# ChargeControllerMainBoard.net
KiCad netlist of a schematic drawn in EAGLE
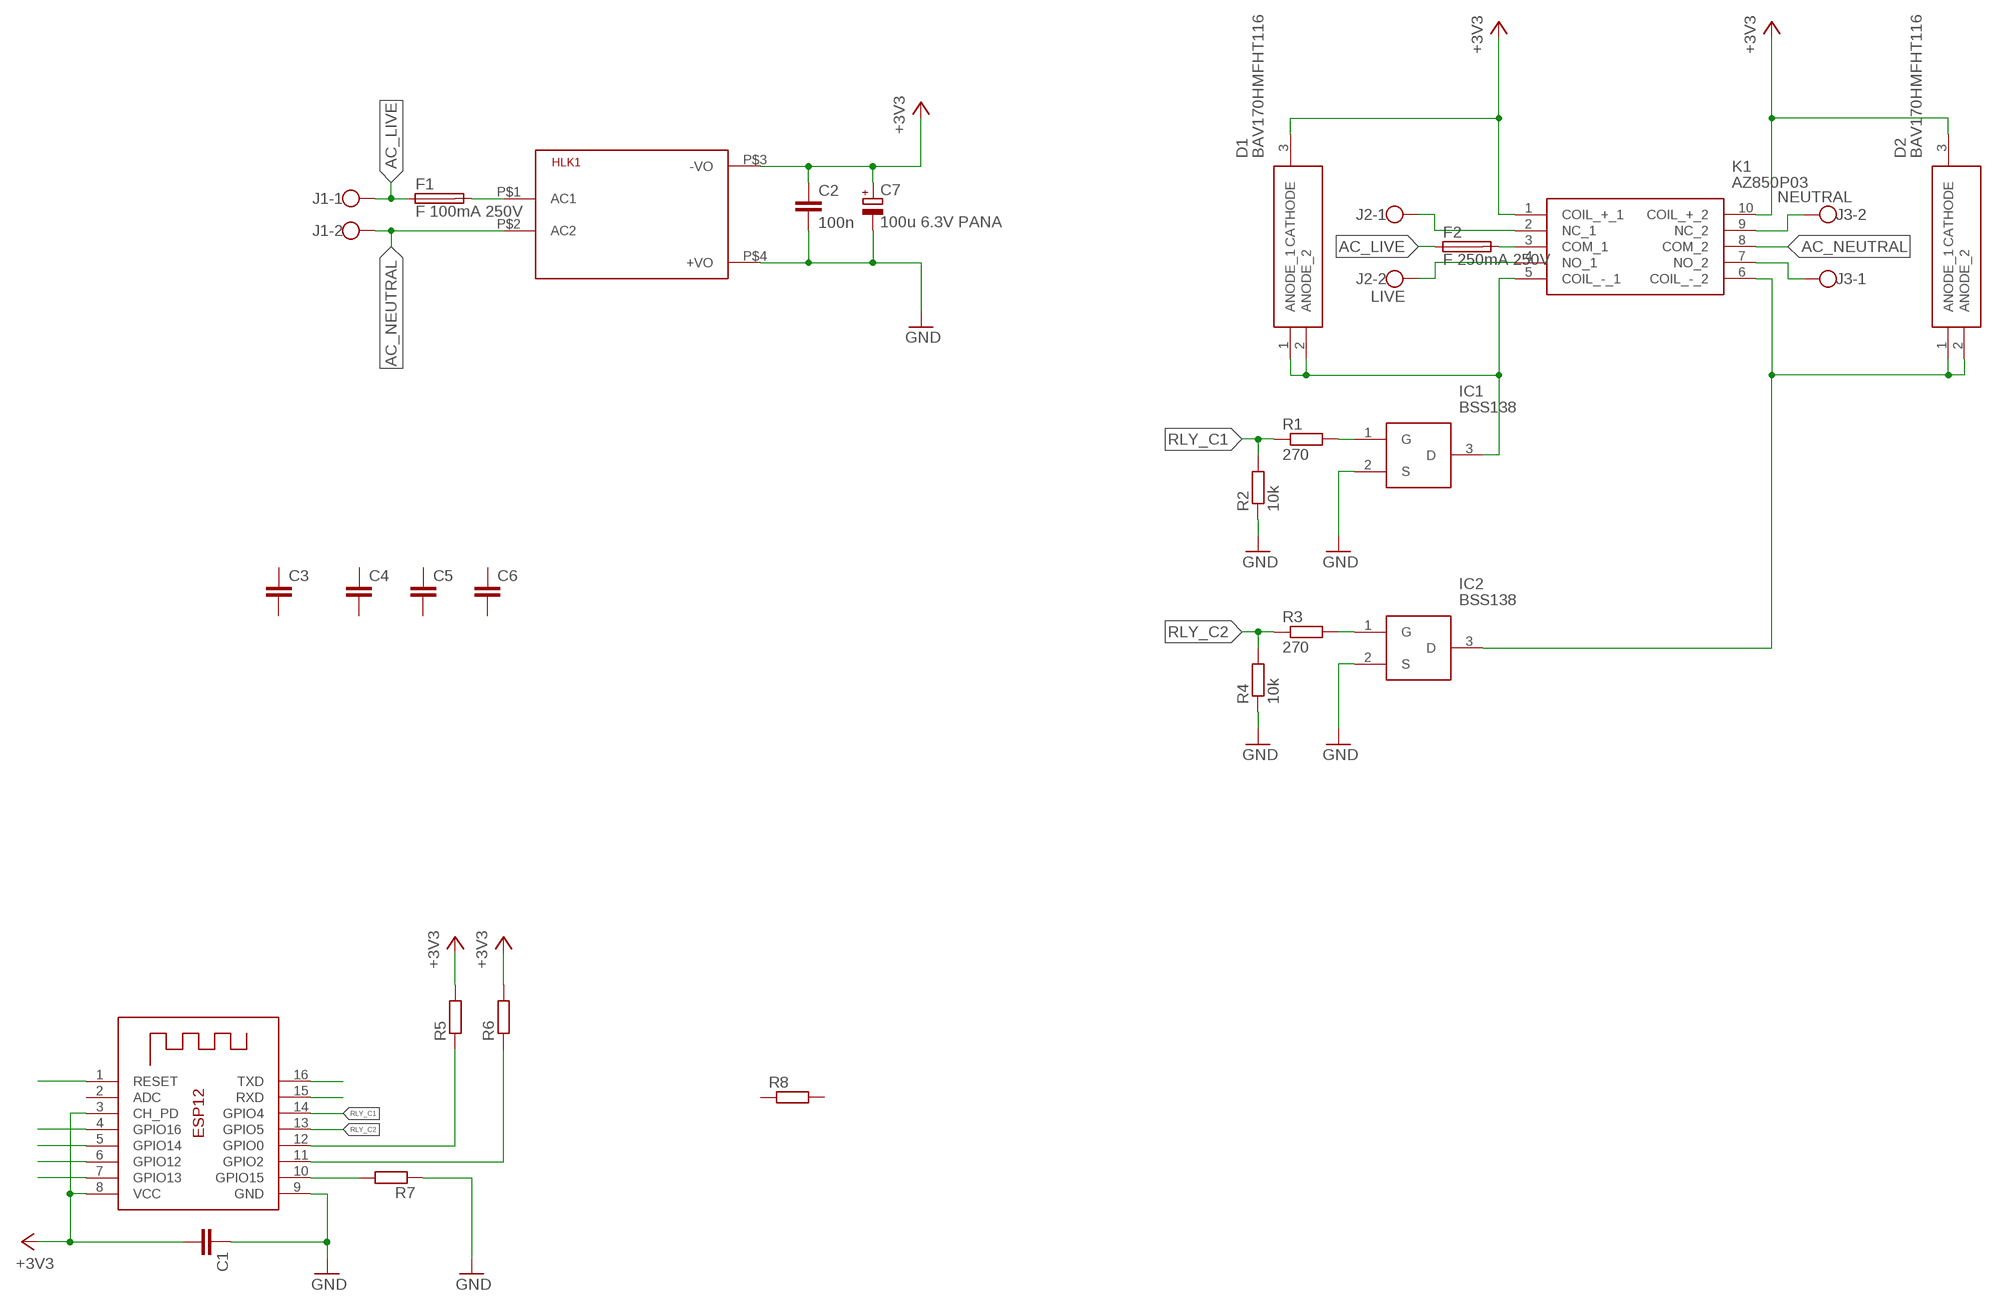
[diagram p0: schematic, sheet 1]

(export (version "E")
  (design (tool "Eeschema 10.0.6"))
  (components
    (comp (ref "C1")
      (value "C-EUC0805")
      (footprint "eagle-import:C0805")
      (libsource (lib "eagle-import") (part "C-EUC0805"))
    )
    (comp (ref "C2")
      (value "100n")
      (footprint "eagle-import:C0805")
      (libsource (lib "eagle-import") (part "C-EUC0805"))
    )
    (comp (ref "C3")
      (value "C-EUC0805")
      (footprint "eagle-import:C0805")
      (libsource (lib "eagle-import") (part "C-EUC0805"))
    )
    (comp (ref "C4")
      (value "C-EUC0805")
      (footprint "eagle-import:C0805")
      (libsource (lib "eagle-import") (part "C-EUC0805"))
    )
    (comp (ref "C5")
      (value "C-EUC0805")
      (footprint "eagle-import:C0805")
      (libsource (lib "eagle-import") (part "C-EUC0805"))
    )
    (comp (ref "C6")
      (value "C-EUC0805")
      (footprint "eagle-import:C0805")
      (libsource (lib "eagle-import") (part "C-EUC0805"))
    )
    (comp (ref "C7")
      (value "100u 6.3V PANA")
      (footprint "eagle-import:PANASONIC_B")
      (libsource (lib "eagle-import") (part "CPOL-EUB"))
    )
    (comp (ref "D1")
      (value "BAV170HMFHT116")
      (footprint "eagle-import:SOT95P240X115-3N")
      (fields (field (name "MOUSER_PART_NUMBER") "755-BAV170HMFHT116"))
      (libsource (lib "eagle-import") (part "BAV170HMFHT116"))
    )
    (comp (ref "D2")
      (value "BAV170HMFHT116")
      (footprint "eagle-import:SOT95P240X115-3N")
      (fields (field (name "MOUSER_PART_NUMBER") "755-BAV170HMFHT116"))
      (libsource (lib "eagle-import") (part "BAV170HMFHT116"))
    )
    (comp (ref "F1")
      (value "F 100mA 250V")
      (footprint "eagle-import:SH22,5")
      (fields (field (name "MF") "SCHURTER") (field (name "MPN") "0031.8201"))
      (libsource (lib "eagle-import") (part "SH22,5"))
    )
    (comp (ref "F2")
      (value "F 250mA 250V")
      (footprint "eagle-import:SH22,5")
      (fields (field (name "MF") "SCHURTER") (field (name "MPN") "0031.8201"))
      (libsource (lib "eagle-import") (part "SH22,5"))
    )
    (comp (ref "HLK1")
      (value "HLK-PM03")
      (footprint "eagle-import:HLK-PM01")
      (libsource (lib "eagle-import") (part "HLK-PM013W"))
    )
    (comp (ref "IC1")
      (value "BSS138")
      (footprint "eagle-import:SOT95P240X120-3N")
      (fields (field (name "MOUSER_PART_NUMBER") "512-BSS138") (field (name "RS_PART_NUMBER") "1241694"))
      (libsource (lib "eagle-import") (part "BSS138"))
    )
    (comp (ref "IC2")
      (value "BSS138")
      (footprint "eagle-import:SOT95P240X120-3N")
      (fields (field (name "MOUSER_PART_NUMBER") "512-BSS138") (field (name "RS_PART_NUMBER") "1241694"))
      (libsource (lib "eagle-import") (part "BSS138"))
    )
    (comp (ref "J1")
      (value "W237-102")
      (footprint "eagle-import:W237-102")
      (fields (field (name "MPN") "237-102"))
      (libsource (lib "eagle-import") (part "W237-102"))
    )
    (comp (ref "J2")
      (value "LIVE")
      (footprint "eagle-import:W237-102")
      (fields (field (name "MPN") "237-102"))
      (libsource (lib "eagle-import") (part "W237-102"))
    )
    (comp (ref "J3")
      (value "NEUTRAL")
      (footprint "eagle-import:W237-102")
      (fields (field (name "MPN") "237-102"))
      (libsource (lib "eagle-import") (part "W237-102"))
    )
    (comp (ref "K1")
      (value "AZ850P03")
      (footprint "eagle-import:DIPS763W51P254L1400H525Q10N")
      (fields (field (name "MANUFACTURER_PART_NUMBER") "AZ850P2&ndash;5"))
      (libsource (lib "eagle-import") (part "AZ850P25"))
    )
    (comp (ref "R1")
      (value "270")
      (footprint "eagle-import:R0805")
      (libsource (lib "eagle-import") (part "R-EU_R0805"))
    )
    (comp (ref "R2")
      (value "10k")
      (footprint "eagle-import:R0805")
      (libsource (lib "eagle-import") (part "R-EU_R0805"))
    )
    (comp (ref "R3")
      (value "270")
      (footprint "eagle-import:R0805")
      (libsource (lib "eagle-import") (part "R-EU_R0805"))
    )
    (comp (ref "R4")
      (value "10k")
      (footprint "eagle-import:R0805")
      (libsource (lib "eagle-import") (part "R-EU_R0805"))
    )
    (comp (ref "R5")
      (value "R-EU_R0805")
      (footprint "eagle-import:R0805")
      (libsource (lib "eagle-import") (part "R-EU_R0805"))
    )
    (comp (ref "R6")
      (value "R-EU_R0805")
      (footprint "eagle-import:R0805")
      (libsource (lib "eagle-import") (part "R-EU_R0805"))
    )
    (comp (ref "R7")
      (value "R-EU_R0805")
      (footprint "eagle-import:R0805")
      (libsource (lib "eagle-import") (part "R-EU_R0805"))
    )
    (comp (ref "R8")
      (value "R-EU_R0805")
      (footprint "eagle-import:R0805")
      (libsource (lib "eagle-import") (part "R-EU_R0805"))
    )
    (comp (ref "X1")
      (value "ESP-12")
      (footprint "eagle-import:ESP-12")
      (libsource (lib "eagle-import") (part "ESP-12"))
    )
  )
  (nets
    (net (code "1") (name "+3V3") (class "Default")
      (node (ref "C1") (pin "2") (pinfunction "2_2") (pintype "passive"))
      (node (ref "C2") (pin "1") (pinfunction "1_1") (pintype "passive"))
      (node (ref "C7") (pin "+") (pinfunction "+_+") (pintype "passive"))
      (node (ref "D1") (pin "3") (pinfunction "CATHODE_3") (pintype "bidirectional"))
      (node (ref "D2") (pin "3") (pinfunction "CATHODE_3") (pintype "bidirectional"))
      (node (ref "HLK1") (pin "P$3") (pinfunction "-VO_P$3") (pintype "bidirectional"))
      (node (ref "K1") (pin "1") (pinfunction "COIL_+_1_1") (pintype "bidirectional"))
      (node (ref "K1") (pin "10") (pinfunction "COIL_+_2_10") (pintype "bidirectional"))
      (node (ref "R5") (pin "2") (pinfunction "2_2") (pintype "passive"))
      (node (ref "R6") (pin "2") (pinfunction "2_2") (pintype "passive"))
      (node (ref "X1") (pin "3") (pinfunction "CH_PD_3") (pintype "input"))
      (node (ref "X1") (pin "8") (pinfunction "VCC_8") (pintype "power_in"))
    )
    (net (code "2") (name "AC_LIVE") (class "Default")
      (node (ref "F1") (pin "1") (pinfunction "1_1") (pintype "passive"))
      (node (ref "F2") (pin "1") (pinfunction "1_1") (pintype "passive"))
      (node (ref "J1") (pin "1") (pinfunction "KL_1") (pintype "passive"))
    )
    (net (code "3") (name "AC_NEUTRAL") (class "Default")
      (node (ref "HLK1") (pin "P$2") (pinfunction "AC2_P$2") (pintype "bidirectional"))
      (node (ref "J1") (pin "2") (pinfunction "KL_2") (pintype "passive"))
      (node (ref "K1") (pin "8") (pinfunction "COM_2_8") (pintype "bidirectional"))
    )
    (net (code "4") (name "GND") (class "Default")
      (node (ref "C1") (pin "1") (pinfunction "1_1") (pintype "passive"))
      (node (ref "C2") (pin "2") (pinfunction "2_2") (pintype "passive"))
      (node (ref "C7") (pin "-") (pinfunction "-_-") (pintype "passive"))
      (node (ref "HLK1") (pin "P$4") (pinfunction "+VO_P$4") (pintype "bidirectional"))
      (node (ref "IC1") (pin "2") (pinfunction "S_2") (pintype "bidirectional"))
      (node (ref "IC2") (pin "2") (pinfunction "S_2") (pintype "bidirectional"))
      (node (ref "R2") (pin "1") (pinfunction "1_1") (pintype "passive"))
      (node (ref "R4") (pin "1") (pinfunction "1_1") (pintype "passive"))
      (node (ref "R7") (pin "1") (pinfunction "1_1") (pintype "passive"))
      (node (ref "X1") (pin "9") (pinfunction "GND_9") (pintype "power_in"))
    )
    (net (code "5") (name "Net-(D1-ANODE_1)") (class "Default")
      (node (ref "D1") (pin "1") (pinfunction "ANODE_1_1") (pintype "bidirectional"))
      (node (ref "D1") (pin "2") (pinfunction "ANODE_2_2") (pintype "bidirectional"))
      (node (ref "IC1") (pin "3") (pinfunction "D_3") (pintype "bidirectional"))
      (node (ref "K1") (pin "5") (pinfunction "COIL_-_1_5") (pintype "bidirectional"))
    )
    (net (code "6") (name "Net-(D2-ANODE_1)") (class "Default")
      (node (ref "D2") (pin "1") (pinfunction "ANODE_1_1") (pintype "bidirectional"))
      (node (ref "D2") (pin "2") (pinfunction "ANODE_2_2") (pintype "bidirectional"))
      (node (ref "IC2") (pin "3") (pinfunction "D_3") (pintype "bidirectional"))
      (node (ref "K1") (pin "6") (pinfunction "COIL_-_2_6") (pintype "bidirectional"))
    )
    (net (code "7") (name "Net-(HLK1-AC1)") (class "Default")
      (node (ref "F1") (pin "2") (pinfunction "2_2") (pintype "passive"))
      (node (ref "HLK1") (pin "P$1") (pinfunction "AC1_P$1") (pintype "bidirectional"))
    )
    (net (code "8") (name "Net-(IC1-G)") (class "Default")
      (node (ref "IC1") (pin "1") (pinfunction "G_1") (pintype "bidirectional"))
      (node (ref "R1") (pin "2") (pinfunction "2_2") (pintype "passive"))
    )
    (net (code "9") (name "Net-(IC2-G)") (class "Default")
      (node (ref "IC2") (pin "1") (pinfunction "G_1") (pintype "bidirectional"))
      (node (ref "R3") (pin "2") (pinfunction "2_2") (pintype "passive"))
    )
    (net (code "10") (name "Net-(J2A-KL)") (class "Default")
      (node (ref "J2") (pin "1") (pinfunction "KL_1") (pintype "passive"))
      (node (ref "K1") (pin "2") (pinfunction "NC_1_2") (pintype "bidirectional"))
    )
    (net (code "11") (name "Net-(J2B-KL)") (class "Default")
      (node (ref "J2") (pin "2") (pinfunction "KL_2") (pintype "passive"))
      (node (ref "K1") (pin "4") (pinfunction "NO_1_4") (pintype "bidirectional"))
    )
    (net (code "12") (name "Net-(J3A-KL)") (class "Default")
      (node (ref "J3") (pin "1") (pinfunction "KL_1") (pintype "passive"))
      (node (ref "K1") (pin "7") (pinfunction "NO_2_7") (pintype "bidirectional"))
    )
    (net (code "13") (name "Net-(J3B-KL)") (class "Default")
      (node (ref "J3") (pin "2") (pinfunction "KL_2") (pintype "passive"))
      (node (ref "K1") (pin "9") (pinfunction "NC_2_9") (pintype "bidirectional"))
    )
    (net (code "14") (name "Net-(K1-COM_1)") (class "Default")
      (node (ref "F2") (pin "2") (pinfunction "2_2") (pintype "passive"))
      (node (ref "K1") (pin "3") (pinfunction "COM_1_3") (pintype "bidirectional"))
    )
    (net (code "15") (name "Net-(X1-GPIO0)") (class "Default")
      (node (ref "R5") (pin "1") (pinfunction "1_1") (pintype "passive"))
      (node (ref "X1") (pin "12") (pinfunction "GPIO0_12") (pintype "bidirectional"))
    )
    (net (code "16") (name "Net-(X1-GPIO2)") (class "Default")
      (node (ref "R6") (pin "1") (pinfunction "1_1") (pintype "passive"))
      (node (ref "X1") (pin "11") (pinfunction "GPIO2_11") (pintype "bidirectional"))
    )
    (net (code "17") (name "Net-(X1-GPIO15)") (class "Default")
      (node (ref "R7") (pin "2") (pinfunction "2_2") (pintype "passive"))
      (node (ref "X1") (pin "10") (pinfunction "GPIO15_10") (pintype "bidirectional"))
    )
    (net (code "18") (name "RLY_C1") (class "Default")
      (node (ref "R1") (pin "1") (pinfunction "1_1") (pintype "passive"))
      (node (ref "R2") (pin "2") (pinfunction "2_2") (pintype "passive"))
      (node (ref "X1") (pin "14") (pinfunction "GPIO4_14") (pintype "bidirectional"))
    )
    (net (code "19") (name "RLY_C2") (class "Default")
      (node (ref "R3") (pin "1") (pinfunction "1_1") (pintype "passive"))
      (node (ref "R4") (pin "2") (pinfunction "2_2") (pintype "passive"))
      (node (ref "X1") (pin "13") (pinfunction "GPIO5_13") (pintype "bidirectional"))
    )
    (net (code "20") (name "unconnected-(C3-Pad1)") (class "Default")
      (node (ref "C3") (pin "1") (pinfunction "1_1") (pintype "passive"))
    )
    (net (code "21") (name "unconnected-(C3-Pad2)") (class "Default")
      (node (ref "C3") (pin "2") (pinfunction "2_2") (pintype "passive"))
    )
    (net (code "22") (name "unconnected-(C4-Pad1)") (class "Default")
      (node (ref "C4") (pin "1") (pinfunction "1_1") (pintype "passive"))
    )
    (net (code "23") (name "unconnected-(C4-Pad2)") (class "Default")
      (node (ref "C4") (pin "2") (pinfunction "2_2") (pintype "passive"))
    )
    (net (code "24") (name "unconnected-(C5-Pad1)") (class "Default")
      (node (ref "C5") (pin "1") (pinfunction "1_1") (pintype "passive"))
    )
    (net (code "25") (name "unconnected-(C5-Pad2)") (class "Default")
      (node (ref "C5") (pin "2") (pinfunction "2_2") (pintype "passive"))
    )
    (net (code "26") (name "unconnected-(C6-Pad1)") (class "Default")
      (node (ref "C6") (pin "1") (pinfunction "1_1") (pintype "passive"))
    )
    (net (code "27") (name "unconnected-(C6-Pad2)") (class "Default")
      (node (ref "C6") (pin "2") (pinfunction "2_2") (pintype "passive"))
    )
    (net (code "28") (name "unconnected-(R8-Pad1)") (class "Default")
      (node (ref "R8") (pin "1") (pinfunction "1_1") (pintype "passive"))
    )
    (net (code "29") (name "unconnected-(R8-Pad2)") (class "Default")
      (node (ref "R8") (pin "2") (pinfunction "2_2") (pintype "passive"))
    )
    (net (code "30") (name "unconnected-(X1-ADC-Pad2)") (class "Default")
      (node (ref "X1") (pin "2") (pinfunction "ADC_2") (pintype "passive"))
    )
    (net (code "31") (name "unconnected-(X1-GPIO12-Pad6)") (class "Default")
      (node (ref "X1") (pin "6") (pinfunction "GPIO12_6") (pintype "bidirectional"))
    )
    (net (code "32") (name "unconnected-(X1-GPIO13-Pad7)") (class "Default")
      (node (ref "X1") (pin "7") (pinfunction "GPIO13_7") (pintype "bidirectional"))
    )
    (net (code "33") (name "unconnected-(X1-GPIO14-Pad5)") (class "Default")
      (node (ref "X1") (pin "5") (pinfunction "GPIO14_5") (pintype "bidirectional"))
    )
    (net (code "34") (name "unconnected-(X1-GPIO16-Pad4)") (class "Default")
      (node (ref "X1") (pin "4") (pinfunction "GPIO16_4") (pintype "bidirectional"))
    )
    (net (code "35") (name "unconnected-(X1-RESET-Pad1)") (class "Default")
      (node (ref "X1") (pin "1") (pinfunction "RESET_1") (pintype "input"))
    )
    (net (code "36") (name "unconnected-(X1-RXD-Pad15)") (class "Default")
      (node (ref "X1") (pin "15") (pinfunction "RXD_15") (pintype "input"))
    )
    (net (code "37") (name "unconnected-(X1-TXD-Pad16)") (class "Default")
      (node (ref "X1") (pin "16") (pinfunction "TXD_16") (pintype "output"))
    )
  )
)
